# Battery_Monitor.net
KiCad netlist of a schematic drawn in EAGLE
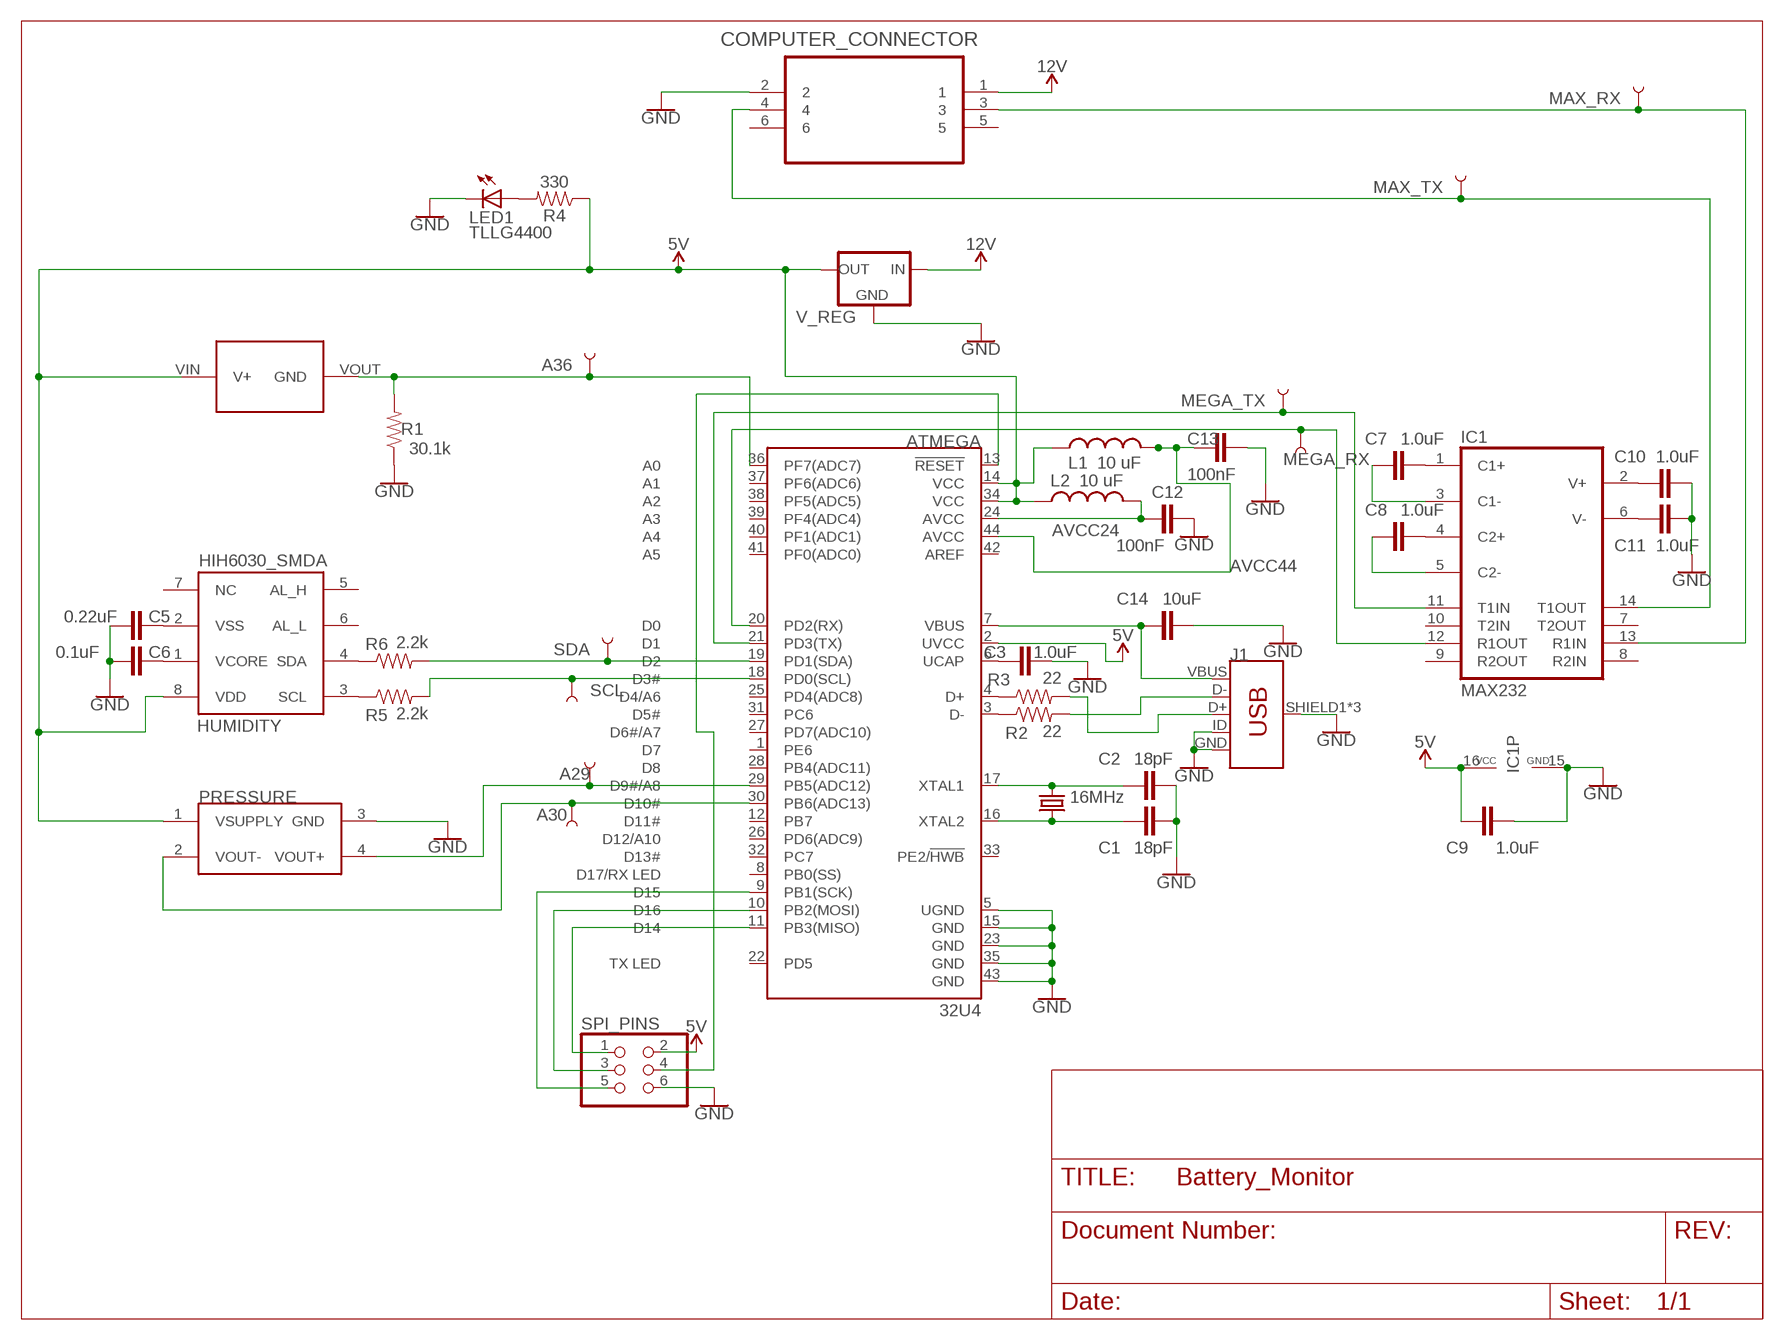
[diagram p0: schematic, sheet 1]

(export (version "E")
  (design (tool "Eeschema 10.0.6"))
  (components
    (comp (ref "16MHZ_CRYSTAL")
      (value "16MHz")
      (footprint "eagle-import:HC49_S")
      (libsource (lib "eagle-import") (part "CRYSTALHC49S"))
    )
    (comp (ref "A29")
      (value "TEST-POINT3X5")
      (footprint "eagle-import:PAD.03X.05")
      (libsource (lib "eagle-import") (part "TEST-POINT3X5"))
    )
    (comp (ref "A30")
      (value "TEST-POINT3X5")
      (footprint "eagle-import:PAD.03X.05")
      (libsource (lib "eagle-import") (part "TEST-POINT3X5"))
    )
    (comp (ref "A36")
      (value "TEST-POINT3X5")
      (footprint "eagle-import:PAD.03X.05")
      (libsource (lib "eagle-import") (part "TEST-POINT3X5"))
    )
    (comp (ref "ATMEGA")
      (value "32U4")
      (footprint "eagle-import:QFN-44")
      (libsource (lib "eagle-import") (part "ATMEGA32U4QFN"))
    )
    (comp (ref "C1")
      (value "18pF")
      (footprint "eagle-import:0603")
      (libsource (lib "eagle-import") (part "18PF-0603-50V-5%"))
    )
    (comp (ref "C2")
      (value "18pF")
      (footprint "eagle-import:0603")
      (libsource (lib "eagle-import") (part "18PF-0603-50V-5%"))
    )
    (comp (ref "C3")
      (value "1.0uF")
      (footprint "eagle-import:0402")
      (libsource (lib "eagle-import") (part "1.0UF-0402-16V-10%"))
    )
    (comp (ref "C5")
      (value "0.22uF")
      (footprint "eagle-import:0603")
      (libsource (lib "eagle-import") (part "0.22UF-0603-25V-10%"))
    )
    (comp (ref "C6")
      (value "0.1uF")
      (footprint "eagle-import:0402")
      (libsource (lib "eagle-import") (part "0.1UF-0402-16V-10%"))
    )
    (comp (ref "C7")
      (value "1.0uF")
      (footprint "eagle-import:0402")
      (libsource (lib "eagle-import") (part "1.0UF-0402-16V-10%"))
    )
    (comp (ref "C8")
      (value "1.0uF")
      (footprint "eagle-import:0402")
      (libsource (lib "eagle-import") (part "1.0UF-0402-16V-10%"))
    )
    (comp (ref "C9")
      (value "1.0uF")
      (footprint "eagle-import:0402")
      (libsource (lib "eagle-import") (part "1.0UF-0402-16V-10%"))
    )
    (comp (ref "C10")
      (value "1.0uF")
      (footprint "eagle-import:0402")
      (libsource (lib "eagle-import") (part "1.0UF-0402-16V-10%"))
    )
    (comp (ref "C11")
      (value "1.0uF")
      (footprint "eagle-import:0402")
      (libsource (lib "eagle-import") (part "1.0UF-0402-16V-10%"))
    )
    (comp (ref "C12")
      (value "100nF")
      (footprint "eagle-import:0402")
      (libsource (lib "eagle-import") (part "1.0UF-0402-16V-10%"))
    )
    (comp (ref "C13")
      (value "100nF")
      (footprint "eagle-import:0402")
      (libsource (lib "eagle-import") (part "1.0UF-0402-16V-10%"))
    )
    (comp (ref "C14")
      (value "10uF")
      (footprint "eagle-import:0603")
      (libsource (lib "eagle-import") (part "10UF-0603-6.3V-20%"))
    )
    (comp (ref "COMPUTER_CONNECTOR")
      (value "52271-0469")
      (footprint "eagle-import:MOLEX_52271-0469")
      (libsource (lib "eagle-import") (part "52271-0469"))
    )
    (comp (ref "FLEX_SQ")
      (value "MOLEX_2WIRE2018")
      (footprint "eagle-import:SMT_MOLEX_PKG")
      (libsource (lib "eagle-import") (part "MOLEX_2WIRE2018"))
    )
    (comp (ref "HUMIDITY")
      (value "HIH6030_SMDA")
      (footprint "eagle-import:SMD-8")
      (libsource (lib "eagle-import") (part "HIH6030_SMDA"))
    )
    (comp (ref "IC1")
      (value "MAX232")
      (footprint "eagle-import:DIL16")
      (fields (field (name "MF") "MAXIM") (field (name "MPN") "MAX232ACPE+"))
      (libsource (lib "eagle-import") (part "MAX232"))
    )
    (comp (ref "J1")
      (value "USB_MICRO-B_FEMALE-SMT")
      (footprint "eagle-import:USB-B-MICRO-SMD")
      (libsource (lib "eagle-import") (part "USB_MICRO-B_FEMALE-SMT"))
    )
    (comp (ref "L1")
      (value "10 uF")
      (footprint "eagle-import:L1812")
      (libsource (lib "eagle-import") (part "L-USL1812"))
    )
    (comp (ref "L2")
      (value "10 uF")
      (footprint "eagle-import:L1812")
      (libsource (lib "eagle-import") (part "L-USL1812"))
    )
    (comp (ref "LED1")
      (value "TLLG4400")
      (footprint "eagle-import:LED3MM")
      (fields (field (name "MF") "VISHAY SEMICONDUCTOR"))
      (libsource (lib "eagle-import") (part "TLLG4400"))
    )
    (comp (ref "MAX_RX")
      (value "TEST-POINT3X5")
      (footprint "eagle-import:PAD.03X.05")
      (libsource (lib "eagle-import") (part "TEST-POINT3X5"))
    )
    (comp (ref "MAX_TX")
      (value "TEST-POINT3X5")
      (footprint "eagle-import:PAD.03X.05")
      (libsource (lib "eagle-import") (part "TEST-POINT3X5"))
    )
    (comp (ref "MEGA_RX")
      (value "TEST-POINT3X5")
      (footprint "eagle-import:PAD.03X.05")
      (libsource (lib "eagle-import") (part "TEST-POINT3X5"))
    )
    (comp (ref "MEGA_TX")
      (value "TEST-POINT3X5")
      (footprint "eagle-import:PAD.03X.05")
      (libsource (lib "eagle-import") (part "TEST-POINT3X5"))
    )
    (comp (ref "PRESSURE")
      (value "HONEYWELL_PRESSURE_SENSOR2018")
      (footprint "eagle-import:4PIN_SMT")
      (libsource (lib "eagle-import") (part "HONEYWELL_PRESSURE_SENSOR2018"))
    )
    (comp (ref "R1")
      (value "30.1k")
      (footprint "eagle-import:0603")
      (libsource (lib "eagle-import") (part "30.1KOHM-0603-1/10W-1%"))
    )
    (comp (ref "R2")
      (value "22")
      (footprint "eagle-import:0402")
      (libsource (lib "eagle-import") (part "22OHM-0402-1/10W-1%"))
    )
    (comp (ref "R3")
      (value "22")
      (footprint "eagle-import:0402")
      (libsource (lib "eagle-import") (part "22OHM-0402-1/10W-1%"))
    )
    (comp (ref "R4")
      (value "330")
      (footprint "eagle-import:0603")
      (libsource (lib "eagle-import") (part "330OHM-0603-1/10W-1%"))
    )
    (comp (ref "R5")
      (value "2.2k")
      (footprint "eagle-import:0603")
      (libsource (lib "eagle-import") (part "2.2KOHM-0603-1/10W-1%"))
    )
    (comp (ref "R6")
      (value "2.2k")
      (footprint "eagle-import:0603")
      (libsource (lib "eagle-import") (part "2.2KOHM-0603-1/10W-1%"))
    )
    (comp (ref "SCL")
      (value "TEST-POINT3X5")
      (footprint "eagle-import:PAD.03X.05")
      (libsource (lib "eagle-import") (part "TEST-POINT3X5"))
    )
    (comp (ref "SDA")
      (value "TEST-POINT3X5")
      (footprint "eagle-import:PAD.03X.05")
      (libsource (lib "eagle-import") (part "TEST-POINT3X5"))
    )
    (comp (ref "SPI_PINS")
      (value "PINHD-2X3")
      (footprint "eagle-import:2X03")
      (libsource (lib "eagle-import") (part "PINHD-2X3"))
    )
    (comp (ref "V_REG")
      (value "DC_DC_78XXA")
      (footprint "eagle-import:DC-DC_CONVERTER_78XX")
      (libsource (lib "eagle-import") (part "DC_DC_78XXA"))
    )
  )
  (nets
    (net (code "1") (name "/AVCC24") (class "Default")
      (node (ref "ATMEGA") (pin "24") (pinfunction "AVCC_24") (pintype "bidirectional"))
      (node (ref "C12") (pin "2") (pinfunction "2_2") (pintype "passive"))
      (node (ref "L2") (pin "2") (pinfunction "2_2") (pintype "passive"))
    )
    (net (code "2") (name "/AVCC44") (class "Default")
      (node (ref "ATMEGA") (pin "44") (pinfunction "AVCC_44") (pintype "bidirectional"))
      (node (ref "C13") (pin "2") (pinfunction "2_2") (pintype "passive"))
      (node (ref "L1") (pin "2") (pinfunction "2_2") (pintype "passive"))
    )
    (net (code "3") (name "5V") (class "Default")
      (node (ref "ATMEGA") (pin "14") (pinfunction "VCC_14") (pintype "bidirectional"))
      (node (ref "ATMEGA") (pin "2") (pinfunction "UVCC_2") (pintype "bidirectional"))
      (node (ref "ATMEGA") (pin "34") (pinfunction "VCC_34") (pintype "bidirectional"))
      (node (ref "C9") (pin "1") (pinfunction "1_1") (pintype "passive"))
      (node (ref "FLEX_SQ") (pin "VIN") (pinfunction "V+_VIN") (pintype "bidirectional"))
      (node (ref "HUMIDITY") (pin "8") (pinfunction "VDD_8") (pintype "bidirectional"))
      (node (ref "IC1") (pin "16") (pinfunction "VCC_16") (pintype "power_in"))
      (node (ref "L1") (pin "1") (pinfunction "1_1") (pintype "passive"))
      (node (ref "L2") (pin "1") (pinfunction "1_1") (pintype "passive"))
      (node (ref "PRESSURE") (pin "1") (pinfunction "VSUPPLY_1") (pintype "bidirectional"))
      (node (ref "R4") (pin "1") (pinfunction "1_1") (pintype "passive"))
      (node (ref "SPI_PINS") (pin "2") (pinfunction "2_2") (pintype "passive"))
      (node (ref "V_REG") (pin "VOUT") (pinfunction "OUT_VOUT") (pintype "passive"))
    )
    (net (code "4") (name "12V") (class "Default")
      (node (ref "COMPUTER_CONNECTOR") (pin "1") (pinfunction "1_1") (pintype "passive"))
      (node (ref "V_REG") (pin "VIN") (pinfunction "IN_VIN") (pintype "input"))
    )
    (net (code "5") (name "GND") (class "Default")
      (node (ref "ATMEGA") (pin "15") (pinfunction "GND_15") (pintype "bidirectional"))
      (node (ref "ATMEGA") (pin "23") (pinfunction "GND_23") (pintype "bidirectional"))
      (node (ref "ATMEGA") (pin "35") (pinfunction "GND_35") (pintype "bidirectional"))
      (node (ref "ATMEGA") (pin "43") (pinfunction "GND_43") (pintype "bidirectional"))
      (node (ref "ATMEGA") (pin "5") (pinfunction "UGND_5") (pintype "bidirectional"))
      (node (ref "C1") (pin "1") (pinfunction "1_1") (pintype "passive"))
      (node (ref "C10") (pin "2") (pinfunction "2_2") (pintype "passive"))
      (node (ref "C11") (pin "2") (pinfunction "2_2") (pintype "passive"))
      (node (ref "C12") (pin "1") (pinfunction "1_1") (pintype "passive"))
      (node (ref "C13") (pin "1") (pinfunction "1_1") (pintype "passive"))
      (node (ref "C14") (pin "2") (pinfunction "2_2") (pintype "passive"))
      (node (ref "C2") (pin "1") (pinfunction "1_1") (pintype "passive"))
      (node (ref "C3") (pin "2") (pinfunction "2_2") (pintype "passive"))
      (node (ref "C5") (pin "1") (pinfunction "1_1") (pintype "passive"))
      (node (ref "C6") (pin "1") (pinfunction "1_1") (pintype "passive"))
      (node (ref "C9") (pin "2") (pinfunction "2_2") (pintype "passive"))
      (node (ref "COMPUTER_CONNECTOR") (pin "2") (pinfunction "2_2") (pintype "passive"))
      (node (ref "IC1") (pin "15") (pinfunction "GND_15") (pintype "power_in"))
      (node (ref "J1") (pin "GND") (pinfunction "GND_GND") (pintype "power_in"))
      (node (ref "J1") (pin "ID") (pinfunction "ID_ID") (pintype "bidirectional"))
      (node (ref "J1") (pin "SHIELD1") (pinfunction "SHIELD_SHIELD1") (pintype "bidirectional"))
      (node (ref "J1") (pin "SHIELD2") (pinfunction "SHIELD_SHIELD2") (pintype "bidirectional"))
      (node (ref "J1") (pin "SHIELD3") (pinfunction "SHIELD_SHIELD3") (pintype "bidirectional"))
      (node (ref "LED1") (pin "K") (pinfunction "C_K") (pintype "passive"))
      (node (ref "PRESSURE") (pin "3") (pinfunction "GND_3") (pintype "bidirectional"))
      (node (ref "R1") (pin "1") (pinfunction "1_1") (pintype "passive"))
      (node (ref "SPI_PINS") (pin "6") (pinfunction "6_6") (pintype "passive"))
      (node (ref "V_REG") (pin "GND") (pinfunction "GND_GND") (pintype "input"))
    )
    (net (code "6") (name "Net-(A29-1)") (class "Default")
      (node (ref "A29") (pin "P$1") (pinfunction "1_P$1") (pintype "bidirectional"))
      (node (ref "ATMEGA") (pin "29") (pinfunction "PB5(ADC12)_29") (pintype "bidirectional"))
      (node (ref "PRESSURE") (pin "4") (pinfunction "VOUT+_4") (pintype "bidirectional"))
    )
    (net (code "7") (name "Net-(A30-1)") (class "Default")
      (node (ref "A30") (pin "P$1") (pinfunction "1_P$1") (pintype "bidirectional"))
      (node (ref "ATMEGA") (pin "30") (pinfunction "PB6(ADC13)_30") (pintype "bidirectional"))
      (node (ref "PRESSURE") (pin "2") (pinfunction "VOUT-_2") (pintype "bidirectional"))
    )
    (net (code "8") (name "Net-(A36-1)") (class "Default")
      (node (ref "A36") (pin "P$1") (pinfunction "1_P$1") (pintype "bidirectional"))
      (node (ref "ATMEGA") (pin "36") (pinfunction "PF7(ADC7)_36") (pintype "bidirectional"))
      (node (ref "FLEX_SQ") (pin "VOUT") (pinfunction "GND_VOUT") (pintype "bidirectional"))
      (node (ref "R1") (pin "2") (pinfunction "2_2") (pintype "passive"))
    )
    (net (code "9") (name "Net-(ATMEGA-D+)") (class "Default")
      (node (ref "ATMEGA") (pin "4") (pinfunction "D+_4") (pintype "bidirectional"))
      (node (ref "R3") (pin "1") (pinfunction "1_1") (pintype "passive"))
    )
    (net (code "10") (name "Net-(ATMEGA-D-)") (class "Default")
      (node (ref "ATMEGA") (pin "3") (pinfunction "D-_3") (pintype "bidirectional"))
      (node (ref "R2") (pin "1") (pinfunction "1_1") (pintype "passive"))
    )
    (net (code "11") (name "Net-(ATMEGA-PB1(SCK))") (class "Default")
      (node (ref "ATMEGA") (pin "9") (pinfunction "PB1(SCK)_9") (pintype "bidirectional"))
      (node (ref "SPI_PINS") (pin "5") (pinfunction "5_5") (pintype "passive"))
    )
    (net (code "12") (name "Net-(ATMEGA-PB2(MOSI))") (class "Default")
      (node (ref "ATMEGA") (pin "10") (pinfunction "PB2(MOSI)_10") (pintype "bidirectional"))
      (node (ref "SPI_PINS") (pin "3") (pinfunction "3_3") (pintype "passive"))
    )
    (net (code "13") (name "Net-(ATMEGA-PB3(MISO))") (class "Default")
      (node (ref "ATMEGA") (pin "11") (pinfunction "PB3(MISO)_11") (pintype "bidirectional"))
      (node (ref "SPI_PINS") (pin "1") (pinfunction "1_1") (pintype "passive"))
    )
    (net (code "14") (name "Net-(ATMEGA-PD0(SCL))") (class "Default")
      (node (ref "ATMEGA") (pin "18") (pinfunction "PD0(SCL)_18") (pintype "bidirectional"))
      (node (ref "R5") (pin "2") (pinfunction "2_2") (pintype "passive"))
      (node (ref "SCL") (pin "P$1") (pinfunction "1_P$1") (pintype "bidirectional"))
    )
    (net (code "15") (name "Net-(ATMEGA-PD1(SDA))") (class "Default")
      (node (ref "ATMEGA") (pin "19") (pinfunction "PD1(SDA)_19") (pintype "bidirectional"))
      (node (ref "R6") (pin "2") (pinfunction "2_2") (pintype "passive"))
      (node (ref "SDA") (pin "P$1") (pinfunction "1_P$1") (pintype "bidirectional"))
    )
    (net (code "16") (name "Net-(ATMEGA-PD2(RX))") (class "Default")
      (node (ref "ATMEGA") (pin "20") (pinfunction "PD2(RX)_20") (pintype "bidirectional"))
      (node (ref "IC1") (pin "12") (pinfunction "R1OUT_12") (pintype "output"))
      (node (ref "MEGA_RX") (pin "P$1") (pinfunction "1_P$1") (pintype "bidirectional"))
    )
    (net (code "17") (name "Net-(ATMEGA-PD3(TX))") (class "Default")
      (node (ref "ATMEGA") (pin "21") (pinfunction "PD3(TX)_21") (pintype "bidirectional"))
      (node (ref "IC1") (pin "11") (pinfunction "T1IN_11") (pintype "input"))
      (node (ref "MEGA_TX") (pin "P$1") (pinfunction "1_P$1") (pintype "bidirectional"))
    )
    (net (code "18") (name "Net-(ATMEGA-UCAP)") (class "Default")
      (node (ref "ATMEGA") (pin "6") (pinfunction "UCAP_6") (pintype "bidirectional"))
      (node (ref "C3") (pin "1") (pinfunction "1_1") (pintype "passive"))
    )
    (net (code "19") (name "Net-(ATMEGA-VBUS)") (class "Default")
      (node (ref "ATMEGA") (pin "7") (pinfunction "VBUS_7") (pintype "bidirectional"))
      (node (ref "C14") (pin "1") (pinfunction "1_1") (pintype "passive"))
      (node (ref "J1") (pin "VBUS") (pinfunction "VBUS_VBUS") (pintype "power_in"))
    )
    (net (code "20") (name "Net-(ATMEGA-XTAL1)") (class "Default")
      (node (ref "16MHZ_CRYSTAL") (pin "1") (pinfunction "1_1") (pintype "passive"))
      (node (ref "ATMEGA") (pin "17") (pinfunction "XTAL1_17") (pintype "bidirectional"))
      (node (ref "C2") (pin "2") (pinfunction "2_2") (pintype "passive"))
    )
    (net (code "21") (name "Net-(ATMEGA-XTAL2)") (class "Default")
      (node (ref "16MHZ_CRYSTAL") (pin "2") (pinfunction "2_2") (pintype "passive"))
      (node (ref "ATMEGA") (pin "16") (pinfunction "XTAL2_16") (pintype "bidirectional"))
      (node (ref "C1") (pin "2") (pinfunction "2_2") (pintype "passive"))
    )
    (net (code "22") (name "Net-(ATMEGA-~{RESET})") (class "Default")
      (node (ref "ATMEGA") (pin "13") (pinfunction "~{RESET}_13") (pintype "bidirectional"))
      (node (ref "SPI_PINS") (pin "4") (pinfunction "4_4") (pintype "passive"))
    )
    (net (code "23") (name "Net-(HUMIDITY-SCL)") (class "Default")
      (node (ref "HUMIDITY") (pin "3") (pinfunction "SCL_3") (pintype "bidirectional"))
      (node (ref "R5") (pin "1") (pinfunction "1_1") (pintype "passive"))
    )
    (net (code "24") (name "Net-(HUMIDITY-SDA)") (class "Default")
      (node (ref "HUMIDITY") (pin "4") (pinfunction "SDA_4") (pintype "bidirectional"))
      (node (ref "R6") (pin "1") (pinfunction "1_1") (pintype "passive"))
    )
    (net (code "25") (name "Net-(HUMIDITY-VCORE)") (class "Default")
      (node (ref "C6") (pin "2") (pinfunction "2_2") (pintype "passive"))
      (node (ref "HUMIDITY") (pin "1") (pinfunction "VCORE_1") (pintype "bidirectional"))
    )
    (net (code "26") (name "Net-(HUMIDITY-VSS)") (class "Default")
      (node (ref "C5") (pin "2") (pinfunction "2_2") (pintype "passive"))
      (node (ref "HUMIDITY") (pin "2") (pinfunction "VSS_2") (pintype "bidirectional"))
    )
    (net (code "27") (name "Net-(IC1A-C1+)") (class "Default")
      (node (ref "C7") (pin "1") (pinfunction "1_1") (pintype "passive"))
      (node (ref "IC1") (pin "1") (pinfunction "C1+_1") (pintype "bidirectional"))
    )
    (net (code "28") (name "Net-(IC1A-C1-)") (class "Default")
      (node (ref "C7") (pin "2") (pinfunction "2_2") (pintype "passive"))
      (node (ref "IC1") (pin "3") (pinfunction "C1-_3") (pintype "bidirectional"))
    )
    (net (code "29") (name "Net-(IC1A-C2+)") (class "Default")
      (node (ref "C8") (pin "1") (pinfunction "1_1") (pintype "passive"))
      (node (ref "IC1") (pin "4") (pinfunction "C2+_4") (pintype "bidirectional"))
    )
    (net (code "30") (name "Net-(IC1A-C2-)") (class "Default")
      (node (ref "C8") (pin "2") (pinfunction "2_2") (pintype "passive"))
      (node (ref "IC1") (pin "5") (pinfunction "C2-_5") (pintype "bidirectional"))
    )
    (net (code "31") (name "Net-(IC1A-R1IN)") (class "Default")
      (node (ref "COMPUTER_CONNECTOR") (pin "3") (pinfunction "3_3") (pintype "passive"))
      (node (ref "IC1") (pin "13") (pinfunction "R1IN_13") (pintype "input"))
      (node (ref "MAX_RX") (pin "P$1") (pinfunction "1_P$1") (pintype "bidirectional"))
    )
    (net (code "32") (name "Net-(IC1A-T1OUT)") (class "Default")
      (node (ref "COMPUTER_CONNECTOR") (pin "4") (pinfunction "4_4") (pintype "passive"))
      (node (ref "IC1") (pin "14") (pinfunction "T1OUT_14") (pintype "output"))
      (node (ref "MAX_TX") (pin "P$1") (pinfunction "1_P$1") (pintype "bidirectional"))
    )
    (net (code "33") (name "Net-(IC1A-V+)") (class "Default")
      (node (ref "C10") (pin "1") (pinfunction "1_1") (pintype "passive"))
      (node (ref "IC1") (pin "2") (pinfunction "V+_2") (pintype "bidirectional"))
    )
    (net (code "34") (name "Net-(IC1A-V-)") (class "Default")
      (node (ref "C11") (pin "1") (pinfunction "1_1") (pintype "passive"))
      (node (ref "IC1") (pin "6") (pinfunction "V-_6") (pintype "bidirectional"))
    )
    (net (code "35") (name "Net-(J1-PadD+)") (class "Default")
      (node (ref "J1") (pin "D+") (pinfunction "D+_D+") (pintype "bidirectional"))
      (node (ref "R3") (pin "2") (pinfunction "2_2") (pintype "passive"))
    )
    (net (code "36") (name "Net-(J1-PadD-)") (class "Default")
      (node (ref "J1") (pin "D-") (pinfunction "D-_D-") (pintype "bidirectional"))
      (node (ref "R2") (pin "2") (pinfunction "2_2") (pintype "passive"))
    )
    (net (code "37") (name "Net-(LED1-PadA)") (class "Default")
      (node (ref "LED1") (pin "A") (pinfunction "A_A") (pintype "passive"))
      (node (ref "R4") (pin "2") (pinfunction "2_2") (pintype "passive"))
    )
    (net (code "38") (name "unconnected-(ATMEGA-AREF-Pad42)") (class "Default")
      (node (ref "ATMEGA") (pin "42") (pinfunction "AREF_42") (pintype "bidirectional"))
    )
    (net (code "39") (name "unconnected-(ATMEGA-PB0(SS)-Pad8)") (class "Default")
      (node (ref "ATMEGA") (pin "8") (pinfunction "PB0(SS)_8") (pintype "bidirectional"))
    )
    (net (code "40") (name "unconnected-(ATMEGA-PB4(ADC11)-Pad28)") (class "Default")
      (node (ref "ATMEGA") (pin "28") (pinfunction "PB4(ADC11)_28") (pintype "bidirectional"))
    )
    (net (code "41") (name "unconnected-(ATMEGA-PB7-Pad12)") (class "Default")
      (node (ref "ATMEGA") (pin "12") (pinfunction "PB7_12") (pintype "bidirectional"))
    )
    (net (code "42") (name "unconnected-(ATMEGA-PC6-Pad31)") (class "Default")
      (node (ref "ATMEGA") (pin "31") (pinfunction "PC6_31") (pintype "bidirectional"))
    )
    (net (code "43") (name "unconnected-(ATMEGA-PC7-Pad32)") (class "Default")
      (node (ref "ATMEGA") (pin "32") (pinfunction "PC7_32") (pintype "bidirectional"))
    )
    (net (code "44") (name "unconnected-(ATMEGA-PD4(ADC8)-Pad25)") (class "Default")
      (node (ref "ATMEGA") (pin "25") (pinfunction "PD4(ADC8)_25") (pintype "bidirectional"))
    )
    (net (code "45") (name "unconnected-(ATMEGA-PD5-Pad22)") (class "Default")
      (node (ref "ATMEGA") (pin "22") (pinfunction "PD5_22") (pintype "bidirectional"))
    )
    (net (code "46") (name "unconnected-(ATMEGA-PD6(ADC9)-Pad26)") (class "Default")
      (node (ref "ATMEGA") (pin "26") (pinfunction "PD6(ADC9)_26") (pintype "bidirectional"))
    )
    (net (code "47") (name "unconnected-(ATMEGA-PD7(ADC10)-Pad27)") (class "Default")
      (node (ref "ATMEGA") (pin "27") (pinfunction "PD7(ADC10)_27") (pintype "bidirectional"))
    )
    (net (code "48") (name "unconnected-(ATMEGA-PE2{slash}~{HWB}-Pad33)") (class "Default")
      (node (ref "ATMEGA") (pin "33") (pinfunction "PE2/~{HWB}_33") (pintype "bidirectional"))
    )
    (net (code "49") (name "unconnected-(ATMEGA-PE6-Pad1)") (class "Default")
      (node (ref "ATMEGA") (pin "1") (pinfunction "PE6_1") (pintype "bidirectional"))
    )
    (net (code "50") (name "unconnected-(ATMEGA-PF0(ADC0)-Pad41)") (class "Default")
      (node (ref "ATMEGA") (pin "41") (pinfunction "PF0(ADC0)_41") (pintype "bidirectional"))
    )
    (net (code "51") (name "unconnected-(ATMEGA-PF1(ADC1)-Pad40)") (class "Default")
      (node (ref "ATMEGA") (pin "40") (pinfunction "PF1(ADC1)_40") (pintype "bidirectional"))
    )
    (net (code "52") (name "unconnected-(ATMEGA-PF4(ADC4)-Pad39)") (class "Default")
      (node (ref "ATMEGA") (pin "39") (pinfunction "PF4(ADC4)_39") (pintype "bidirectional"))
    )
    (net (code "53") (name "unconnected-(ATMEGA-PF5(ADC5)-Pad38)") (class "Default")
      (node (ref "ATMEGA") (pin "38") (pinfunction "PF5(ADC5)_38") (pintype "bidirectional"))
    )
    (net (code "54") (name "unconnected-(ATMEGA-PF6(ADC6)-Pad37)") (class "Default")
      (node (ref "ATMEGA") (pin "37") (pinfunction "PF6(ADC6)_37") (pintype "bidirectional"))
    )
    (net (code "55") (name "unconnected-(COMPUTER_CONNECTOR-Pad5)") (class "Default")
      (node (ref "COMPUTER_CONNECTOR") (pin "5") (pinfunction "5_5") (pintype "passive"))
    )
    (net (code "56") (name "unconnected-(COMPUTER_CONNECTOR-Pad6)") (class "Default")
      (node (ref "COMPUTER_CONNECTOR") (pin "6") (pinfunction "6_6") (pintype "passive"))
    )
    (net (code "57") (name "unconnected-(HUMIDITY-AL_H-Pad5)") (class "Default")
      (node (ref "HUMIDITY") (pin "5") (pinfunction "AL_H_5") (pintype "bidirectional"))
    )
    (net (code "58") (name "unconnected-(HUMIDITY-AL_L-Pad6)") (class "Default")
      (node (ref "HUMIDITY") (pin "6") (pinfunction "AL_L_6") (pintype "bidirectional"))
    )
    (net (code "59") (name "unconnected-(HUMIDITY-NC-Pad7)") (class "Default")
      (node (ref "HUMIDITY") (pin "7") (pinfunction "NC_7") (pintype "bidirectional"))
    )
    (net (code "60") (name "unconnected-(IC1A-R2IN-Pad8)") (class "Default")
      (node (ref "IC1") (pin "8") (pinfunction "R2IN_8") (pintype "input"))
    )
    (net (code "61") (name "unconnected-(IC1A-R2OUT-Pad9)") (class "Default")
      (node (ref "IC1") (pin "9") (pinfunction "R2OUT_9") (pintype "output"))
    )
    (net (code "62") (name "unconnected-(IC1A-T2IN-Pad10)") (class "Default")
      (node (ref "IC1") (pin "10") (pinfunction "T2IN_10") (pintype "input"))
    )
    (net (code "63") (name "unconnected-(IC1A-T2OUT-Pad7)") (class "Default")
      (node (ref "IC1") (pin "7") (pinfunction "T2OUT_7") (pintype "output"))
    )
  )
)
